# Sheet1.net
KiCad netlist of a schematic drawn in Altium Designer
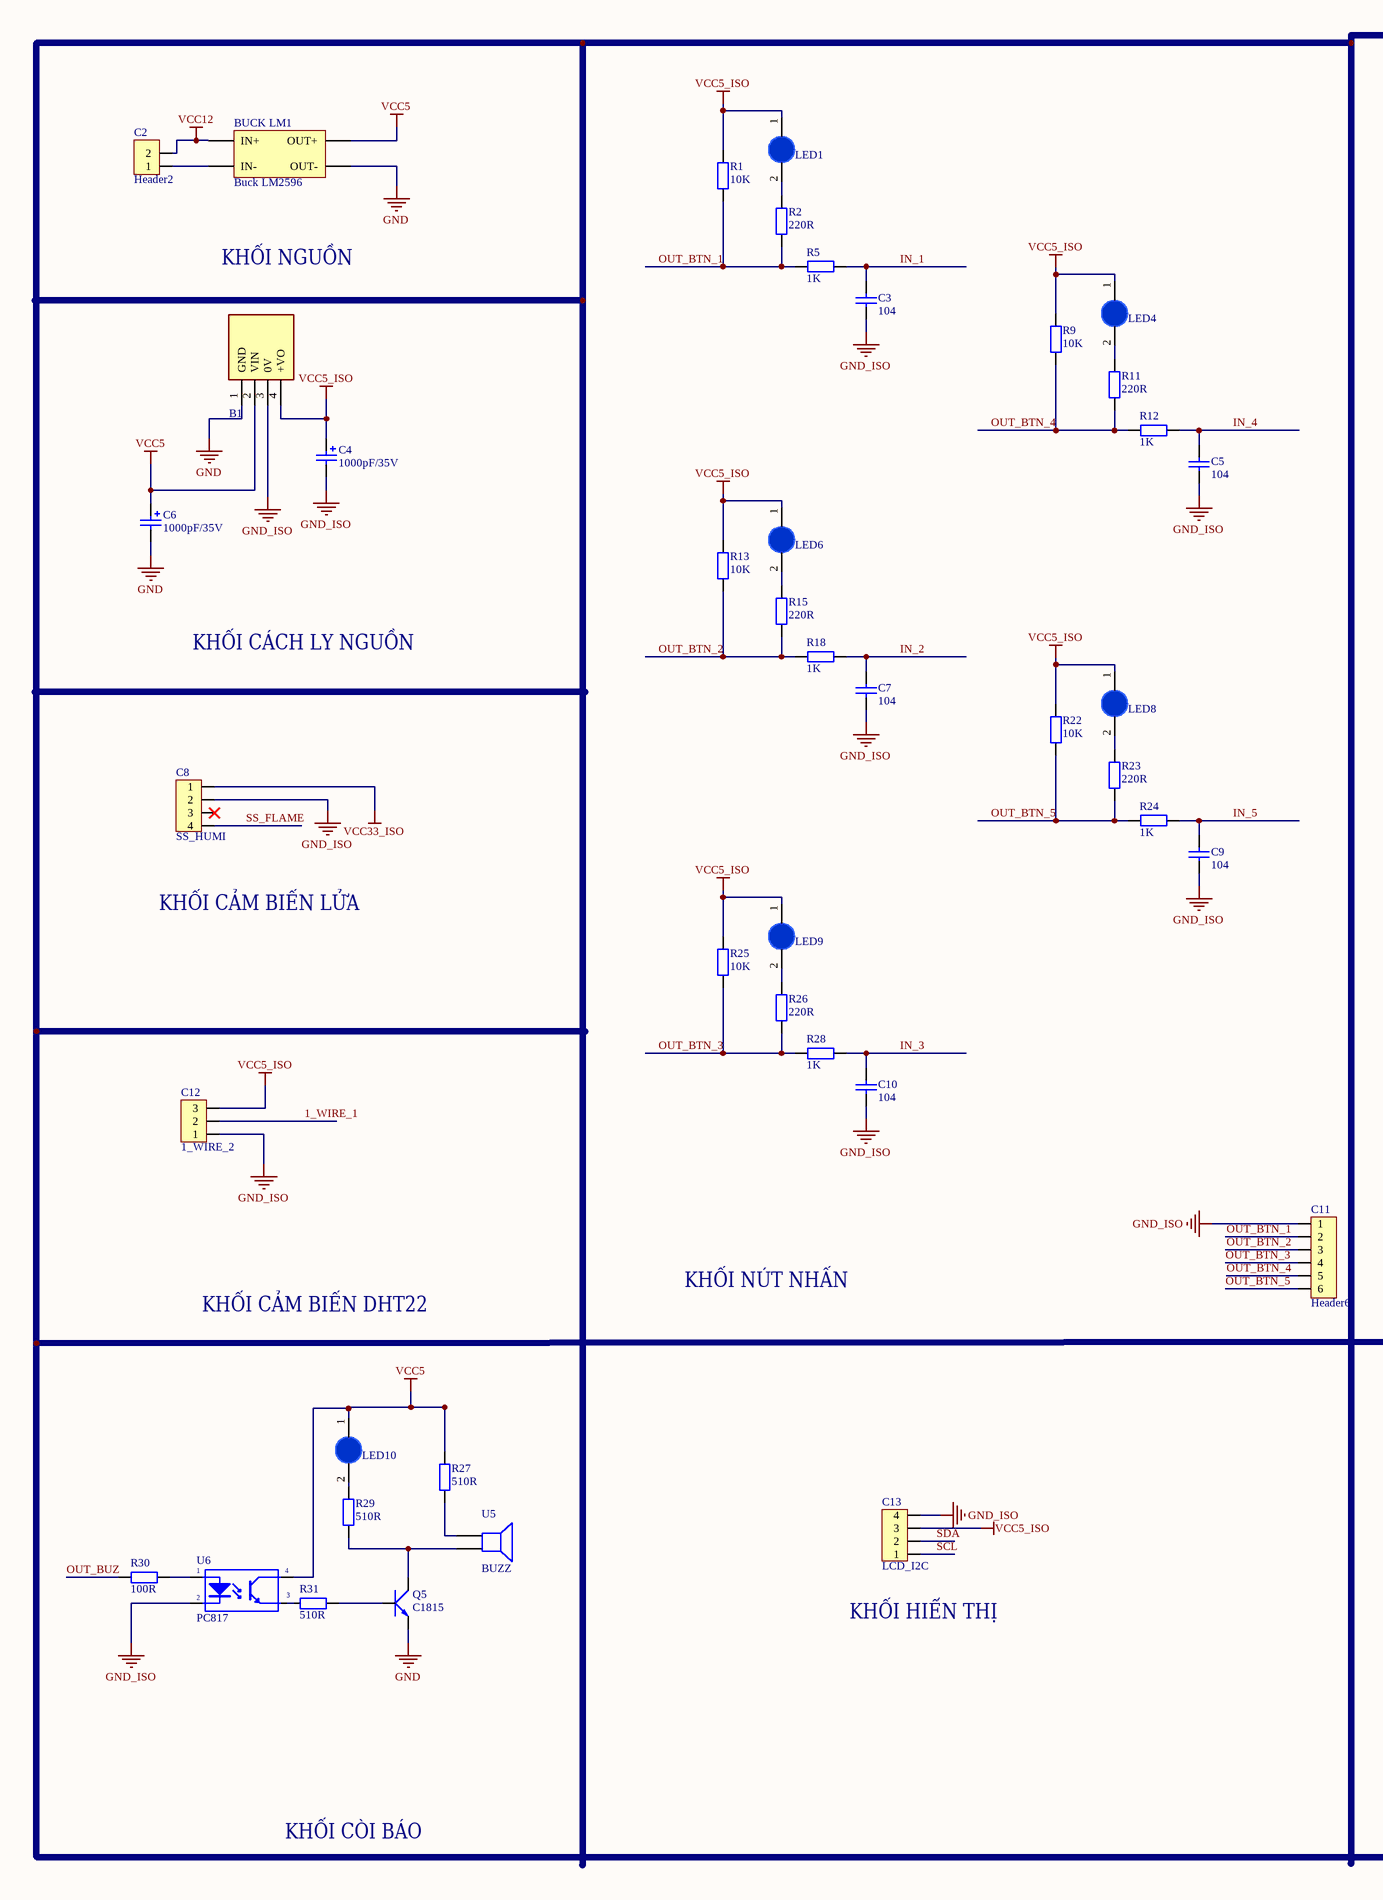
[diagram p0: Sheet1.SchDoc, left]
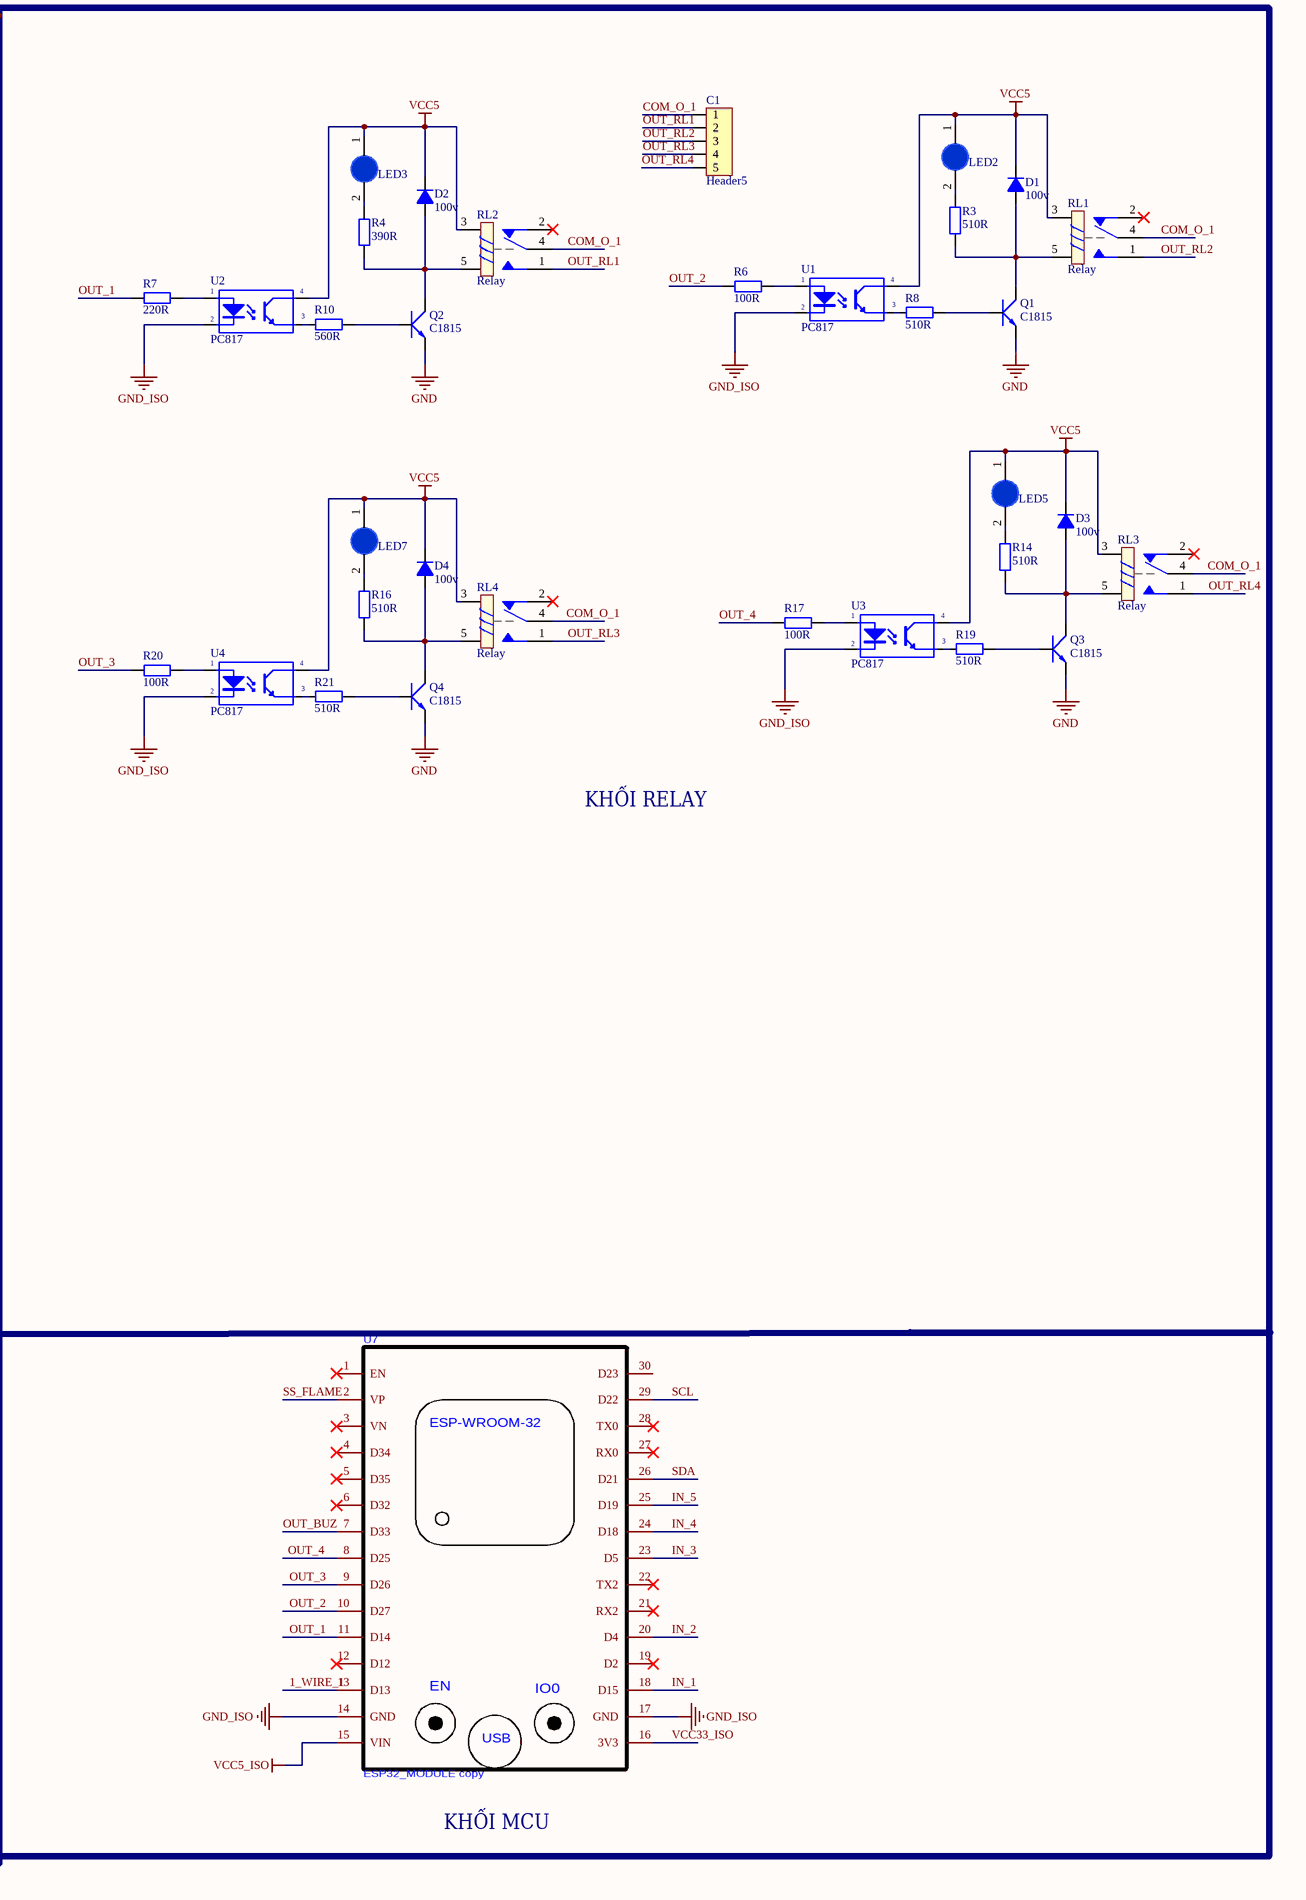
[diagram p1: Sheet1.SchDoc, right]

(export (version "E")
  (design (tool "Eeschema 10.0.6"))
  (components
    (comp (ref "B1")
      (value "B0505S1W")
      (footprint "B0505S1W")
      (description "Power Supply")
      (fields (field (name "MANUFACTURER_PART_NUMBER") "B0505S-1W"))
      (libsource (lib "myLib_v1") (part "B0505S1W"))
    )
    (comp (ref "BUCK LM1")
      (value "Buck LM2596")
      (footprint "BUCK LM2596")
      (libsource (lib "myLib_v1") (part "Buck LM2596"))
    )
    (comp (ref "C1")
      (value "Header5")
      (footprint "Header5")
      (description "Header IDC, 5 x 1 Pin Vertical 2.54mm Pitch (Non-Boxed, Male)")
      (fields
        (field (name "MANUFACTURER") "Würth Elektronik eiSos GmbH")
        (field (name "PARTNO") "613002143121")
        (field (name "CREATED BY") "Karrer Zheng")
      )
      (libsource (lib "myLib_v1") (part "Header5"))
    )
    (comp (ref "C2")
      (value "Header2")
      (footprint "Header2")
      (description "Header IDC, 2 x 1 Pin Vertical 2.54mm Pitch (Non-Boxed, Male)")
      (fields
        (field (name "MANUFACTURER") "Würth Elektronik eiSos GmbH")
        (field (name "PARTNO") "613002143121")
        (field (name "CREATED BY") "Karrer Zheng")
      )
      (libsource (lib "myLib_v1") (part "Header2"))
    )
    (comp (ref "C3")
      (value "104")
      (footprint "tu gom")
      (description "Cắm")
      (libsource (lib "Altium_Lib_by_KhueNguyenCreator") (part "Tu gom 104 50V"))
    )
    (comp (ref "C4")
      (value "1000pF/35V")
      (footprint "CP2/5")
      (description "Polarized Capacitor (Surface Mount)")
      (fields (field (name "Comment") "Cap Pol3") (field (name "PUBLISHER") "Altium Limited"))
      (libsource (lib "myLib_v1") (part "Cap Pol3"))
    )
    (comp (ref "C5")
      (value "104")
      (footprint "tu gom")
      (description "Cắm")
      (libsource (lib "Altium_Lib_by_KhueNguyenCreator") (part "Tu gom 104 50V"))
    )
    (comp (ref "C6")
      (value "1000pF/35V")
      (footprint "CP2/5")
      (description "Polarized Capacitor (Surface Mount)")
      (fields (field (name "Comment") "Cap Pol3") (field (name "PUBLISHER") "Altium Limited"))
      (libsource (lib "myLib_v1") (part "Cap Pol3"))
    )
    (comp (ref "C7")
      (value "104")
      (footprint "tu gom")
      (description "Cắm")
      (libsource (lib "Altium_Lib_by_KhueNguyenCreator") (part "Tu gom 104 50V"))
    )
    (comp (ref "C8")
      (value "SS_HUMI")
      (footprint "Header4")
      (description "Header IDC, 4 x 1 Pin Vertical 2.54mm Pitch (Non-Boxed, Male)")
      (fields
        (field (name "MANUFACTURER") "Würth Elektronik eiSos GmbH")
        (field (name "PARTNO") "613002143121")
        (field (name "CREATED BY") "Karrer Zheng")
      )
      (libsource (lib "myLib_v1") (part "Header4"))
    )
    (comp (ref "C9")
      (value "104")
      (footprint "tu gom")
      (description "Cắm")
      (libsource (lib "Altium_Lib_by_KhueNguyenCreator") (part "Tu gom 104 50V"))
    )
    (comp (ref "C10")
      (value "104")
      (footprint "tu gom")
      (description "Cắm")
      (libsource (lib "Altium_Lib_by_KhueNguyenCreator") (part "Tu gom 104 50V"))
    )
    (comp (ref "C11")
      (value "Header6")
      (footprint "HDR6")
      (description "Header IDC, 6 x 1 Pin Vertical 2.54mm Pitch (Non-Boxed, Male)")
      (fields
        (field (name "MANUFACTURER") "Würth Elektronik eiSos GmbH")
        (field (name "PARTNO") "613002143121")
        (field (name "CREATED BY") "Karrer Zheng")
      )
      (libsource (lib "myLib_v1") (part "Header6"))
    )
    (comp (ref "C12")
      (value "1_WIRE_2")
      (footprint "Header3")
      (description "Header IDC, 3 x 1 Pin Vertical 2.54mm Pitch (Non-Boxed, Male)")
      (fields
        (field (name "MANUFACTURER") "Würth Elektronik eiSos GmbH")
        (field (name "PARTNO") "613002143121")
        (field (name "CREATED BY") "Karrer Zheng")
      )
      (libsource (lib "myLib_v1") (part "Header3"))
    )
    (comp (ref "C13")
      (value "LCD_I2C")
      (footprint "Header4")
      (description "Header IDC, 4 x 1 Pin Vertical 2.54mm Pitch (Non-Boxed, Male)")
      (fields
        (field (name "MANUFACTURER") "Würth Elektronik eiSos GmbH")
        (field (name "PARTNO") "613002143121")
        (field (name "CREATED BY") "Karrer Zheng")
      )
      (libsource (lib "") (part "Header4_1"))
    )
    (comp (ref "D1")
      (value "100v")
      (footprint "DIODE 0.5A")
      (description "Cắm")
      (libsource (lib "Altium_Lib_by_KhueNguyenCreator") (part "Diode 1N4148"))
    )
    (comp (ref "D2")
      (value "100v")
      (footprint "DIODE 0.5A")
      (description "Cắm")
      (libsource (lib "Altium_Lib_by_KhueNguyenCreator") (part "Diode 1N4148"))
    )
    (comp (ref "D3")
      (value "100v")
      (footprint "DIODE 0.5A")
      (description "Cắm")
      (libsource (lib "Altium_Lib_by_KhueNguyenCreator") (part "Diode 1N4148"))
    )
    (comp (ref "D4")
      (value "100v")
      (footprint "DIODE 0.5A")
      (description "Cắm")
      (libsource (lib "Altium_Lib_by_KhueNguyenCreator") (part "Diode 1N4148"))
    )
    (comp (ref "LED1")
      (value "LED 3mm")
      (footprint "LED-3MM-BLUE")
      (description "Cắm")
      (libsource (lib "myLib_v1") (part "LED 3mm Xanh Duong"))
    )
    (comp (ref "LED2")
      (value "LED 3mm")
      (footprint "LED-3MM-BLUE")
      (description "Cắm")
      (libsource (lib "myLib_v1") (part "LED 3mm Xanh Duong"))
    )
    (comp (ref "LED3")
      (value "LED 3mm")
      (footprint "LED-3MM-BLUE")
      (description "Cắm")
      (libsource (lib "myLib_v1") (part "LED 3mm Xanh Duong"))
    )
    (comp (ref "LED4")
      (value "LED 3mm")
      (footprint "LED-3MM-BLUE")
      (description "Cắm")
      (libsource (lib "myLib_v1") (part "LED 3mm Xanh Duong"))
    )
    (comp (ref "LED5")
      (value "LED 3mm")
      (footprint "LED-3MM-BLUE")
      (description "Cắm")
      (libsource (lib "myLib_v1") (part "LED 3mm Xanh Duong"))
    )
    (comp (ref "LED6")
      (value "LED 3mm")
      (footprint "LED-3MM-BLUE")
      (description "Cắm")
      (libsource (lib "myLib_v1") (part "LED 3mm Xanh Duong"))
    )
    (comp (ref "LED7")
      (value "LED 3mm")
      (footprint "LED-3MM-BLUE")
      (description "Cắm")
      (libsource (lib "myLib_v1") (part "LED 3mm Xanh Duong"))
    )
    (comp (ref "LED8")
      (value "LED 3mm")
      (footprint "LED-3MM-BLUE")
      (description "Cắm")
      (libsource (lib "myLib_v1") (part "LED 3mm Xanh Duong"))
    )
    (comp (ref "LED9")
      (value "LED 3mm")
      (footprint "LED-3MM-BLUE")
      (description "Cắm")
      (libsource (lib "myLib_v1") (part "LED 3mm Xanh Duong"))
    )
    (comp (ref "LED10")
      (value "LED 3mm")
      (footprint "LED-3MM-BLUE")
      (description "Cắm")
      (libsource (lib "myLib_v1") (part "LED 3mm Xanh Duong"))
    )
    (comp (ref "Q1")
      (value "C1815")
      (footprint "C1815_cam")
      (description "NPN 600mW, ECB")
      (libsource (lib "myLib_v1") (part "C1815"))
    )
    (comp (ref "Q2")
      (value "C1815")
      (footprint "C1815_cam")
      (description "NPN 600mW, ECB")
      (libsource (lib "myLib_v1") (part "C1815"))
    )
    (comp (ref "Q3")
      (value "C1815")
      (footprint "C1815_cam")
      (description "NPN 600mW, ECB")
      (libsource (lib "myLib_v1") (part "C1815"))
    )
    (comp (ref "Q4")
      (value "C1815")
      (footprint "C1815_cam")
      (description "NPN 600mW, ECB")
      (libsource (lib "myLib_v1") (part "C1815"))
    )
    (comp (ref "Q5")
      (value "C1815")
      (footprint "C1815_cam")
      (description "NPN 600mW, ECB")
      (libsource (lib "myLib_v1") (part "C1815"))
    )
    (comp (ref "R1")
      (value "10K")
      (footprint "R1/4W")
      (description "Resistor 1/4W")
      (libsource (lib "myLib_v1") (part "R1/4W"))
    )
    (comp (ref "R2")
      (value "220R")
      (footprint "R1/4W")
      (description "Resistor 1/4W")
      (libsource (lib "myLib_v1") (part "R1/4W"))
    )
    (comp (ref "R3")
      (value "510R")
      (footprint "R1/4W")
      (description "Resistor 1/4W")
      (libsource (lib "myLib_v1") (part "R1/4W"))
    )
    (comp (ref "R4")
      (value "390R")
      (footprint "R1/4W")
      (description "Resistor 1/4W")
      (libsource (lib "myLib_v1") (part "R1/4W"))
    )
    (comp (ref "R5")
      (value "1K")
      (footprint "R1/4W")
      (description "Resistor 1/4W")
      (libsource (lib "myLib_v1") (part "R1/4W"))
    )
    (comp (ref "R6")
      (value "100R")
      (footprint "R1/4W")
      (description "Resistor 1/4W")
      (libsource (lib "myLib_v1") (part "R1/4W"))
    )
    (comp (ref "R7")
      (value "220R")
      (footprint "R1/4W")
      (description "Resistor 1/4W")
      (libsource (lib "myLib_v1") (part "R1/4W"))
    )
    (comp (ref "R8")
      (value "510R")
      (footprint "R1/4W")
      (description "Resistor 1/4W")
      (libsource (lib "myLib_v1") (part "R1/4W"))
    )
    (comp (ref "R9")
      (value "10K")
      (footprint "R1/4W")
      (description "Resistor 1/4W")
      (libsource (lib "myLib_v1") (part "R1/4W"))
    )
    (comp (ref "R10")
      (value "560R")
      (footprint "R1/4W")
      (description "Resistor 1/4W")
      (libsource (lib "myLib_v1") (part "R1/4W"))
    )
    (comp (ref "R11")
      (value "220R")
      (footprint "R1/4W")
      (description "Resistor 1/4W")
      (libsource (lib "myLib_v1") (part "R1/4W"))
    )
    (comp (ref "R12")
      (value "1K")
      (footprint "R1/4W")
      (description "Resistor 1/4W")
      (libsource (lib "myLib_v1") (part "R1/4W"))
    )
    (comp (ref "R13")
      (value "10K")
      (footprint "R1/4W")
      (description "Resistor 1/4W")
      (libsource (lib "myLib_v1") (part "R1/4W"))
    )
    (comp (ref "R14")
      (value "510R")
      (footprint "R1/4W")
      (description "Resistor 1/4W")
      (libsource (lib "myLib_v1") (part "R1/4W"))
    )
    (comp (ref "R15")
      (value "220R")
      (footprint "R1/4W")
      (description "Resistor 1/4W")
      (libsource (lib "myLib_v1") (part "R1/4W"))
    )
    (comp (ref "R16")
      (value "510R")
      (footprint "R1/4W")
      (description "Resistor 1/4W")
      (libsource (lib "myLib_v1") (part "R1/4W"))
    )
    (comp (ref "R17")
      (value "100R")
      (footprint "R1/4W")
      (description "Resistor 1/4W")
      (libsource (lib "myLib_v1") (part "R1/4W"))
    )
    (comp (ref "R18")
      (value "1K")
      (footprint "R1/4W")
      (description "Resistor 1/4W")
      (libsource (lib "myLib_v1") (part "R1/4W"))
    )
    (comp (ref "R19")
      (value "510R")
      (footprint "R1/4W")
      (description "Resistor 1/4W")
      (libsource (lib "myLib_v1") (part "R1/4W"))
    )
    (comp (ref "R20")
      (value "100R")
      (footprint "R1/4W")
      (description "Resistor 1/4W")
      (libsource (lib "myLib_v1") (part "R1/4W"))
    )
    (comp (ref "R21")
      (value "510R")
      (footprint "R1/4W")
      (description "Resistor 1/4W")
      (libsource (lib "myLib_v1") (part "R1/4W"))
    )
    (comp (ref "R22")
      (value "10K")
      (footprint "R1/4W")
      (description "Resistor 1/4W")
      (libsource (lib "myLib_v1") (part "R1/4W"))
    )
    (comp (ref "R23")
      (value "220R")
      (footprint "R1/4W")
      (description "Resistor 1/4W")
      (libsource (lib "myLib_v1") (part "R1/4W"))
    )
    (comp (ref "R24")
      (value "1K")
      (footprint "R1/4W")
      (description "Resistor 1/4W")
      (libsource (lib "myLib_v1") (part "R1/4W"))
    )
    (comp (ref "R25")
      (value "10K")
      (footprint "R1/4W")
      (description "Resistor 1/4W")
      (libsource (lib "myLib_v1") (part "R1/4W"))
    )
    (comp (ref "R26")
      (value "220R")
      (footprint "R1/4W")
      (description "Resistor 1/4W")
      (libsource (lib "myLib_v1") (part "R1/4W"))
    )
    (comp (ref "R27")
      (value "510R")
      (footprint "R1/4W")
      (description "Resistor 1/4W")
      (libsource (lib "myLib_v1") (part "R1/4W"))
    )
    (comp (ref "R28")
      (value "1K")
      (footprint "R1/4W")
      (description "Resistor 1/4W")
      (libsource (lib "myLib_v1") (part "R1/4W"))
    )
    (comp (ref "R29")
      (value "510R")
      (footprint "R1/4W")
      (description "Resistor 1/4W")
      (libsource (lib "myLib_v1") (part "R1/4W"))
    )
    (comp (ref "R30")
      (value "100R")
      (footprint "R1/4W")
      (description "Resistor 1/4W")
      (libsource (lib "myLib_v1") (part "R1/4W"))
    )
    (comp (ref "R31")
      (value "510R")
      (footprint "R1/4W")
      (description "Resistor 1/4W")
      (libsource (lib "myLib_v1") (part "R1/4W"))
    )
    (comp (ref "RL1")
      (value "Relay")
      (footprint "RELAY_SRA_05VDC_SL_C")
      (description "Relay 5 Chan")
      (libsource (lib "myLib_v1") (part "RL_SRA-05VDC-SL-C"))
    )
    (comp (ref "RL2")
      (value "Relay")
      (footprint "RELAY_SRA_05VDC_SL_C")
      (description "Relay 5 Chan")
      (libsource (lib "myLib_v1") (part "RL_SRA-05VDC-SL-C"))
    )
    (comp (ref "RL3")
      (value "Relay")
      (footprint "RELAY_SRA_05VDC_SL_C")
      (description "Relay 5 Chan")
      (libsource (lib "myLib_v1") (part "RL_SRA-05VDC-SL-C"))
    )
    (comp (ref "RL4")
      (value "Relay")
      (footprint "RELAY_SRA_05VDC_SL_C")
      (description "Relay 5 Chan")
      (libsource (lib "myLib_v1") (part "RL_SRA-05VDC-SL-C"))
    )
    (comp (ref "U1")
      (value "PC817")
      (footprint "DIP4/W0.3")
      (description "Single Opto")
      (libsource (lib "myLib_v1") (part "PC817"))
    )
    (comp (ref "U2")
      (value "PC817")
      (footprint "DIP4/W0.3")
      (description "Single Opto")
      (libsource (lib "myLib_v1") (part "PC817"))
    )
    (comp (ref "U3")
      (value "PC817")
      (footprint "DIP4/W0.3")
      (description "Single Opto")
      (libsource (lib "myLib_v1") (part "PC817"))
    )
    (comp (ref "U4")
      (value "PC817")
      (footprint "DIP4/W0.3")
      (description "Single Opto")
      (libsource (lib "myLib_v1") (part "PC817"))
    )
    (comp (ref "U5")
      (value "BUZZ")
      (footprint "BUZZER_D9_TH")
      (description "Loudspeaker")
      (libsource (lib "BYTECH_HW_LIB_2019 (1)") (part "Speaker"))
    )
    (comp (ref "U6")
      (value "PC817")
      (footprint "DIP4/W0.3")
      (description "Single Opto")
      (libsource (lib "myLib_v1") (part "PC817"))
    )
    (comp (ref "U7")
      (value "ESP32_MODULE copy")
      (footprint "ESP32-WIFIMODULE-FOOTPRINT")
      (libsource (lib "myLib_v1") (part "ESP32_MODULE copy"))
    )
  )
  (nets
    (net (code "1") (name "/1_WIRE_1") (class "Default")
      (node (ref "C12") (pin "2") (pinfunction "2_2") (pintype "passive"))
      (node (ref "U7") (pin "13") (pinfunction "D13_13") (pintype "passive"))
    )
    (net (code "2") (name "/COM_O_1") (class "Default")
      (node (ref "C1") (pin "1") (pinfunction "1_1") (pintype "passive"))
      (node (ref "RL1") (pin "4") (pinfunction "4_4") (pintype "passive"))
      (node (ref "RL2") (pin "4") (pinfunction "4_4") (pintype "passive"))
      (node (ref "RL3") (pin "4") (pinfunction "4_4") (pintype "passive"))
      (node (ref "RL4") (pin "4") (pinfunction "4_4") (pintype "passive"))
    )
    (net (code "3") (name "/IN_1") (class "Default")
      (node (ref "C3") (pin "1") (pinfunction "1_1") (pintype "passive"))
      (node (ref "R5") (pin "1") (pinfunction "1_1") (pintype "passive"))
      (node (ref "U7") (pin "18") (pinfunction "D15_18") (pintype "passive"))
    )
    (net (code "4") (name "/IN_2") (class "Default")
      (node (ref "C7") (pin "1") (pinfunction "1_1") (pintype "passive"))
      (node (ref "R18") (pin "1") (pinfunction "1_1") (pintype "passive"))
      (node (ref "U7") (pin "20") (pinfunction "D4_20") (pintype "passive"))
    )
    (net (code "5") (name "/IN_3") (class "Default")
      (node (ref "C10") (pin "1") (pinfunction "1_1") (pintype "passive"))
      (node (ref "R28") (pin "1") (pinfunction "1_1") (pintype "passive"))
      (node (ref "U7") (pin "23") (pinfunction "D5_23") (pintype "passive"))
    )
    (net (code "6") (name "/IN_4") (class "Default")
      (node (ref "C5") (pin "1") (pinfunction "1_1") (pintype "passive"))
      (node (ref "R12") (pin "1") (pinfunction "1_1") (pintype "passive"))
      (node (ref "U7") (pin "24") (pinfunction "D18_24") (pintype "passive"))
    )
    (net (code "7") (name "/IN_5") (class "Default")
      (node (ref "C9") (pin "1") (pinfunction "1_1") (pintype "passive"))
      (node (ref "R24") (pin "1") (pinfunction "1_1") (pintype "passive"))
      (node (ref "U7") (pin "25") (pinfunction "D19_25") (pintype "passive"))
    )
    (net (code "8") (name "/OUT_1") (class "Default")
      (node (ref "R7") (pin "1") (pinfunction "1_1") (pintype "passive"))
      (node (ref "U7") (pin "11") (pinfunction "D14_11") (pintype "passive"))
    )
    (net (code "9") (name "/OUT_2") (class "Default")
      (node (ref "R6") (pin "1") (pinfunction "1_1") (pintype "passive"))
      (node (ref "U7") (pin "10") (pinfunction "D27_10") (pintype "passive"))
    )
    (net (code "10") (name "/OUT_3") (class "Default")
      (node (ref "R20") (pin "1") (pinfunction "1_1") (pintype "passive"))
      (node (ref "U7") (pin "9") (pinfunction "D26_9") (pintype "passive"))
    )
    (net (code "11") (name "/OUT_4") (class "Default")
      (node (ref "R17") (pin "1") (pinfunction "1_1") (pintype "passive"))
      (node (ref "U7") (pin "8") (pinfunction "D25_8") (pintype "passive"))
    )
    (net (code "12") (name "/OUT_BTN_1") (class "Default")
      (node (ref "C11") (pin "2") (pinfunction "2_2") (pintype "passive"))
      (node (ref "R1") (pin "1") (pinfunction "1_1") (pintype "passive"))
      (node (ref "R2") (pin "1") (pinfunction "1_1") (pintype "passive"))
      (node (ref "R5") (pin "2") (pinfunction "2_2") (pintype "passive"))
    )
    (net (code "13") (name "/OUT_BTN_2") (class "Default")
      (node (ref "C11") (pin "3") (pinfunction "3_3") (pintype "passive"))
      (node (ref "R13") (pin "1") (pinfunction "1_1") (pintype "passive"))
      (node (ref "R15") (pin "1") (pinfunction "1_1") (pintype "passive"))
      (node (ref "R18") (pin "2") (pinfunction "2_2") (pintype "passive"))
    )
    (net (code "14") (name "/OUT_BTN_3") (class "Default")
      (node (ref "C11") (pin "4") (pinfunction "4_4") (pintype "passive"))
      (node (ref "R25") (pin "1") (pinfunction "1_1") (pintype "passive"))
      (node (ref "R26") (pin "1") (pinfunction "1_1") (pintype "passive"))
      (node (ref "R28") (pin "2") (pinfunction "2_2") (pintype "passive"))
    )
    (net (code "15") (name "/OUT_BTN_4") (class "Default")
      (node (ref "C11") (pin "5") (pinfunction "5_5") (pintype "passive"))
      (node (ref "R11") (pin "1") (pinfunction "1_1") (pintype "passive"))
      (node (ref "R12") (pin "2") (pinfunction "2_2") (pintype "passive"))
      (node (ref "R9") (pin "1") (pinfunction "1_1") (pintype "passive"))
    )
    (net (code "16") (name "/OUT_BTN_5") (class "Default")
      (node (ref "C11") (pin "6") (pinfunction "6_6") (pintype "passive"))
      (node (ref "R22") (pin "1") (pinfunction "1_1") (pintype "passive"))
      (node (ref "R23") (pin "1") (pinfunction "1_1") (pintype "passive"))
      (node (ref "R24") (pin "2") (pinfunction "2_2") (pintype "passive"))
    )
    (net (code "17") (name "/OUT_BUZ") (class "Default")
      (node (ref "R30") (pin "1") (pinfunction "1_1") (pintype "passive"))
      (node (ref "U7") (pin "7") (pinfunction "D33_7") (pintype "passive"))
    )
    (net (code "18") (name "/OUT_RL1") (class "Default")
      (node (ref "C1") (pin "2") (pinfunction "2_2") (pintype "passive"))
      (node (ref "RL2") (pin "1") (pinfunction "1_1") (pintype "passive"))
    )
    (net (code "19") (name "/OUT_RL2") (class "Default")
      (node (ref "C1") (pin "3") (pinfunction "3_3") (pintype "passive"))
      (node (ref "RL1") (pin "1") (pinfunction "1_1") (pintype "passive"))
    )
    (net (code "20") (name "/OUT_RL3") (class "Default")
      (node (ref "C1") (pin "4") (pinfunction "4_4") (pintype "passive"))
      (node (ref "RL4") (pin "1") (pinfunction "1_1") (pintype "passive"))
    )
    (net (code "21") (name "/OUT_RL4") (class "Default")
      (node (ref "C1") (pin "5") (pinfunction "5_5") (pintype "passive"))
      (node (ref "RL3") (pin "1") (pinfunction "1_1") (pintype "passive"))
    )
    (net (code "22") (name "/SCL") (class "Default")
      (node (ref "C13") (pin "1") (pinfunction "1_1") (pintype "passive"))
      (node (ref "U7") (pin "29") (pinfunction "D22_29") (pintype "passive"))
    )
    (net (code "23") (name "/SDA") (class "Default")
      (node (ref "C13") (pin "2") (pinfunction "2_2") (pintype "passive"))
      (node (ref "U7") (pin "26") (pinfunction "D21_26") (pintype "passive"))
    )
    (net (code "24") (name "/SS_FLAME") (class "Default")
      (node (ref "C8") (pin "4") (pinfunction "4_4") (pintype "passive"))
      (node (ref "U7") (pin "2") (pinfunction "VP_2") (pintype "passive"))
    )
    (net (code "25") (name "GND") (class "Default")
      (node (ref "B1") (pin "1") (pinfunction "GND_1") (pintype "passive"))
      (node (ref "BUCK LM1") (pin "3") (pinfunction "OUT-_3") (pintype "passive"))
      (node (ref "C6") (pin "2") (pinfunction "2_2") (pintype "passive"))
      (node (ref "Q1") (pin "1") (pinfunction "E_1") (pintype "passive"))
      (node (ref "Q2") (pin "1") (pinfunction "E_1") (pintype "passive"))
      (node (ref "Q3") (pin "1") (pinfunction "E_1") (pintype "passive"))
      (node (ref "Q4") (pin "1") (pinfunction "E_1") (pintype "passive"))
      (node (ref "Q5") (pin "1") (pinfunction "E_1") (pintype "passive"))
    )
    (net (code "26") (name "GND_ISO") (class "Default")
      (node (ref "B1") (pin "3") (pinfunction "0V_3") (pintype "passive"))
      (node (ref "C10") (pin "2") (pinfunction "2_2") (pintype "passive"))
      (node (ref "C11") (pin "1") (pinfunction "1_1") (pintype "passive"))
      (node (ref "C12") (pin "1") (pinfunction "1_1") (pintype "passive"))
      (node (ref "C13") (pin "4") (pinfunction "4_4") (pintype "passive"))
      (node (ref "C3") (pin "2") (pinfunction "2_2") (pintype "passive"))
      (node (ref "C4") (pin "2") (pinfunction "2_2") (pintype "passive"))
      (node (ref "C5") (pin "2") (pinfunction "2_2") (pintype "passive"))
      (node (ref "C7") (pin "2") (pinfunction "2_2") (pintype "passive"))
      (node (ref "C8") (pin "2") (pinfunction "2_2") (pintype "passive"))
      (node (ref "C9") (pin "2") (pinfunction "2_2") (pintype "passive"))
      (node (ref "U1") (pin "2") (pinfunction "K_2") (pintype "passive"))
      (node (ref "U2") (pin "2") (pinfunction "K_2") (pintype "passive"))
      (node (ref "U3") (pin "2") (pinfunction "K_2") (pintype "passive"))
      (node (ref "U4") (pin "2") (pinfunction "K_2") (pintype "passive"))
      (node (ref "U6") (pin "2") (pinfunction "K_2") (pintype "passive"))
      (node (ref "U7") (pin "14") (pinfunction "GND_14") (pintype "passive"))
      (node (ref "U7") (pin "17") (pinfunction "GND_17") (pintype "passive"))
    )
    (net (code "27") (name "Net-(BUCK LM1-IN-)") (class "Default")
      (node (ref "BUCK LM1") (pin "2") (pinfunction "IN-_2") (pintype "passive"))
      (node (ref "C2") (pin "1") (pinfunction "1_1") (pintype "passive"))
    )
    (net (code "28") (name "Net-(D1-A)") (class "Default")
      (node (ref "D1") (pin "1") (pinfunction "A_1") (pintype "passive"))
      (node (ref "Q1") (pin "2") (pinfunction "C_2") (pintype "passive"))
      (node (ref "R3") (pin "2") (pinfunction "2_2") (pintype "passive"))
      (node (ref "RL1") (pin "5") (pinfunction "5_5") (pintype "passive"))
    )
    (net (code "29") (name "Net-(D2-A)") (class "Default")
      (node (ref "D2") (pin "1") (pinfunction "A_1") (pintype "passive"))
      (node (ref "Q2") (pin "2") (pinfunction "C_2") (pintype "passive"))
      (node (ref "R4") (pin "2") (pinfunction "2_2") (pintype "passive"))
      (node (ref "RL2") (pin "5") (pinfunction "5_5") (pintype "passive"))
    )
    (net (code "30") (name "Net-(D3-A)") (class "Default")
      (node (ref "D3") (pin "1") (pinfunction "A_1") (pintype "passive"))
      (node (ref "Q3") (pin "2") (pinfunction "C_2") (pintype "passive"))
      (node (ref "R14") (pin "2") (pinfunction "2_2") (pintype "passive"))
      (node (ref "RL3") (pin "5") (pinfunction "5_5") (pintype "passive"))
    )
    (net (code "31") (name "Net-(D4-A)") (class "Default")
      (node (ref "D4") (pin "1") (pinfunction "A_1") (pintype "passive"))
      (node (ref "Q4") (pin "2") (pinfunction "C_2") (pintype "passive"))
      (node (ref "R16") (pin "2") (pinfunction "2_2") (pintype "passive"))
      (node (ref "RL4") (pin "5") (pinfunction "5_5") (pintype "passive"))
    )
    (net (code "32") (name "Net-(LED1-K)") (class "Default")
      (node (ref "LED1") (pin "2") (pinfunction "K_2") (pintype "passive"))
      (node (ref "R2") (pin "2") (pinfunction "2_2") (pintype "passive"))
    )
    (net (code "33") (name "Net-(LED2-K)") (class "Default")
      (node (ref "LED2") (pin "2") (pinfunction "K_2") (pintype "passive"))
      (node (ref "R3") (pin "1") (pinfunction "1_1") (pintype "passive"))
    )
    (net (code "34") (name "Net-(LED3-K)") (class "Default")
      (node (ref "LED3") (pin "2") (pinfunction "K_2") (pintype "passive"))
      (node (ref "R4") (pin "1") (pinfunction "1_1") (pintype "passive"))
    )
    (net (code "35") (name "Net-(LED4-K)") (class "Default")
      (node (ref "LED4") (pin "2") (pinfunction "K_2") (pintype "passive"))
      (node (ref "R11") (pin "2") (pinfunction "2_2") (pintype "passive"))
    )
    (net (code "36") (name "Net-(LED5-K)") (class "Default")
      (node (ref "LED5") (pin "2") (pinfunction "K_2") (pintype "passive"))
      (node (ref "R14") (pin "1") (pinfunction "1_1") (pintype "passive"))
    )
    (net (code "37") (name "Net-(LED6-K)") (class "Default")
      (node (ref "LED6") (pin "2") (pinfunction "K_2") (pintype "passive"))
      (node (ref "R15") (pin "2") (pinfunction "2_2") (pintype "passive"))
    )
    (net (code "38") (name "Net-(LED7-K)") (class "Default")
      (node (ref "LED7") (pin "2") (pinfunction "K_2") (pintype "passive"))
      (node (ref "R16") (pin "1") (pinfunction "1_1") (pintype "passive"))
    )
    (net (code "39") (name "Net-(LED8-K)") (class "Default")
      (node (ref "LED8") (pin "2") (pinfunction "K_2") (pintype "passive"))
      (node (ref "R23") (pin "2") (pinfunction "2_2") (pintype "passive"))
    )
    (net (code "40") (name "Net-(LED9-K)") (class "Default")
      (node (ref "LED9") (pin "2") (pinfunction "K_2") (pintype "passive"))
      (node (ref "R26") (pin "2") (pinfunction "2_2") (pintype "passive"))
    )
    (net (code "41") (name "Net-(LED10-K)") (class "Default")
      (node (ref "LED10") (pin "2") (pinfunction "K_2") (pintype "passive"))
      (node (ref "R29") (pin "1") (pinfunction "1_1") (pintype "passive"))
    )
    (net (code "42") (name "Net-(Q1-B)") (class "Default")
      (node (ref "Q1") (pin "3") (pinfunction "B_3") (pintype "passive"))
      (node (ref "R8") (pin "2") (pinfunction "2_2") (pintype "passive"))
    )
    (net (code "43") (name "Net-(Q2-B)") (class "Default")
      (node (ref "Q2") (pin "3") (pinfunction "B_3") (pintype "passive"))
      (node (ref "R10") (pin "2") (pinfunction "2_2") (pintype "passive"))
    )
    (net (code "44") (name "Net-(Q3-B)") (class "Default")
      (node (ref "Q3") (pin "3") (pinfunction "B_3") (pintype "passive"))
      (node (ref "R19") (pin "2") (pinfunction "2_2") (pintype "passive"))
    )
    (net (code "45") (name "Net-(Q4-B)") (class "Default")
      (node (ref "Q4") (pin "3") (pinfunction "B_3") (pintype "passive"))
      (node (ref "R21") (pin "2") (pinfunction "2_2") (pintype "passive"))
    )
    (net (code "46") (name "Net-(Q5-B)") (class "Default")
      (node (ref "Q5") (pin "3") (pinfunction "B_3") (pintype "passive"))
      (node (ref "R31") (pin "2") (pinfunction "2_2") (pintype "passive"))
    )
    (net (code "47") (name "Net-(Q5-C)") (class "Default")
      (node (ref "Q5") (pin "2") (pinfunction "C_2") (pintype "passive"))
      (node (ref "R29") (pin "2") (pinfunction "2_2") (pintype "passive"))
      (node (ref "U5") (pin "2") (pinfunction "2_2") (pintype "passive"))
    )
    (net (code "48") (name "Net-(R27-Pad2)") (class "Default")
      (node (ref "R27") (pin "2") (pinfunction "2_2") (pintype "passive"))
      (node (ref "U5") (pin "1") (pinfunction "1_1") (pintype "passive"))
    )
    (net (code "49") (name "Net-(U1-A)") (class "Default")
      (node (ref "R6") (pin "2") (pinfunction "2_2") (pintype "passive"))
      (node (ref "U1") (pin "1") (pinfunction "A_1") (pintype "passive"))
    )
    (net (code "50") (name "Net-(U1-E)") (class "Default")
      (node (ref "R8") (pin "1") (pinfunction "1_1") (pintype "passive"))
      (node (ref "U1") (pin "3") (pinfunction "E_3") (pintype "passive"))
    )
    (net (code "51") (name "Net-(U2-A)") (class "Default")
      (node (ref "R7") (pin "2") (pinfunction "2_2") (pintype "passive"))
      (node (ref "U2") (pin "1") (pinfunction "A_1") (pintype "passive"))
    )
    (net (code "52") (name "Net-(U2-E)") (class "Default")
      (node (ref "R10") (pin "1") (pinfunction "1_1") (pintype "passive"))
      (node (ref "U2") (pin "3") (pinfunction "E_3") (pintype "passive"))
    )
    (net (code "53") (name "Net-(U3-A)") (class "Default")
      (node (ref "R17") (pin "2") (pinfunction "2_2") (pintype "passive"))
      (node (ref "U3") (pin "1") (pinfunction "A_1") (pintype "passive"))
    )
    (net (code "54") (name "Net-(U3-E)") (class "Default")
      (node (ref "R19") (pin "1") (pinfunction "1_1") (pintype "passive"))
      (node (ref "U3") (pin "3") (pinfunction "E_3") (pintype "passive"))
    )
    (net (code "55") (name "Net-(U4-A)") (class "Default")
      (node (ref "R20") (pin "2") (pinfunction "2_2") (pintype "passive"))
      (node (ref "U4") (pin "1") (pinfunction "A_1") (pintype "passive"))
    )
    (net (code "56") (name "Net-(U4-E)") (class "Default")
      (node (ref "R21") (pin "1") (pinfunction "1_1") (pintype "passive"))
      (node (ref "U4") (pin "3") (pinfunction "E_3") (pintype "passive"))
    )
    (net (code "57") (name "Net-(U6-A)") (class "Default")
      (node (ref "R30") (pin "2") (pinfunction "2_2") (pintype "passive"))
      (node (ref "U6") (pin "1") (pinfunction "A_1") (pintype "passive"))
    )
    (net (code "58") (name "Net-(U6-E)") (class "Default")
      (node (ref "R31") (pin "1") (pinfunction "1_1") (pintype "passive"))
      (node (ref "U6") (pin "3") (pinfunction "E_3") (pintype "passive"))
    )
    (net (code "59") (name "VCC5") (class "Default")
      (node (ref "B1") (pin "2") (pinfunction "VIN_2") (pintype "passive"))
      (node (ref "BUCK LM1") (pin "4") (pinfunction "OUT+_4") (pintype "passive"))
      (node (ref "C6") (pin "1") (pinfunction "1_1") (pintype "passive"))
      (node (ref "D1") (pin "2") (pinfunction "K_2") (pintype "passive"))
      (node (ref "D2") (pin "2") (pinfunction "K_2") (pintype "passive"))
      (node (ref "D3") (pin "2") (pinfunction "K_2") (pintype "passive"))
      (node (ref "D4") (pin "2") (pinfunction "K_2") (pintype "passive"))
      (node (ref "LED10") (pin "1") (pinfunction "A_1") (pintype "passive"))
      (node (ref "LED2") (pin "1") (pinfunction "A_1") (pintype "passive"))
      (node (ref "LED3") (pin "1") (pinfunction "A_1") (pintype "passive"))
      (node (ref "LED5") (pin "1") (pinfunction "A_1") (pintype "passive"))
      (node (ref "LED7") (pin "1") (pinfunction "A_1") (pintype "passive"))
      (node (ref "R27") (pin "1") (pinfunction "1_1") (pintype "passive"))
      (node (ref "RL1") (pin "3") (pinfunction "3_3") (pintype "passive"))
      (node (ref "RL2") (pin "3") (pinfunction "3_3") (pintype "passive"))
      (node (ref "RL3") (pin "3") (pinfunction "3_3") (pintype "passive"))
      (node (ref "RL4") (pin "3") (pinfunction "3_3") (pintype "passive"))
      (node (ref "U1") (pin "4") (pinfunction "C_4") (pintype "passive"))
      (node (ref "U2") (pin "4") (pinfunction "C_4") (pintype "passive"))
      (node (ref "U3") (pin "4") (pinfunction "C_4") (pintype "passive"))
      (node (ref "U4") (pin "4") (pinfunction "C_4") (pintype "passive"))
      (node (ref "U6") (pin "4") (pinfunction "C_4") (pintype "passive"))
    )
    (net (code "60") (name "VCC5_ISO") (class "Default")
      (node (ref "B1") (pin "4") (pinfunction "+VO_4") (pintype "passive"))
      (node (ref "C12") (pin "3") (pinfunction "3_3") (pintype "passive"))
      (node (ref "C13") (pin "3") (pinfunction "3_3") (pintype "passive"))
      (node (ref "C4") (pin "1") (pinfunction "1_1") (pintype "passive"))
      (node (ref "LED1") (pin "1") (pinfunction "A_1") (pintype "passive"))
      (node (ref "LED4") (pin "1") (pinfunction "A_1") (pintype "passive"))
      (node (ref "LED6") (pin "1") (pinfunction "A_1") (pintype "passive"))
      (node (ref "LED8") (pin "1") (pinfunction "A_1") (pintype "passive"))
      (node (ref "LED9") (pin "1") (pinfunction "A_1") (pintype "passive"))
      (node (ref "R1") (pin "2") (pinfunction "2_2") (pintype "passive"))
      (node (ref "R13") (pin "2") (pinfunction "2_2") (pintype "passive"))
      (node (ref "R22") (pin "2") (pinfunction "2_2") (pintype "passive"))
      (node (ref "R25") (pin "2") (pinfunction "2_2") (pintype "passive"))
      (node (ref "R9") (pin "2") (pinfunction "2_2") (pintype "passive"))
      (node (ref "U7") (pin "15") (pinfunction "VIN_15") (pintype "passive"))
    )
    (net (code "61") (name "VCC12") (class "Default")
      (node (ref "BUCK LM1") (pin "1") (pinfunction "IN+_1") (pintype "passive"))
      (node (ref "C2") (pin "2") (pinfunction "2_2") (pintype "passive"))
    )
    (net (code "62") (name "VCC33_ISO") (class "Default")
      (node (ref "C8") (pin "1") (pinfunction "1_1") (pintype "passive"))
      (node (ref "U7") (pin "16") (pinfunction "3V3_16") (pintype "passive"))
    )
    (net (code "63") (name "unconnected-(C8-Pad3)") (class "Default")
      (node (ref "C8") (pin "3") (pinfunction "3_3") (pintype "passive+no_connect"))
    )
    (net (code "64") (name "unconnected-(RL1-Pad2)") (class "Default")
      (node (ref "RL1") (pin "2") (pinfunction "2_2") (pintype "passive+no_connect"))
    )
    (net (code "65") (name "unconnected-(RL2-Pad2)") (class "Default")
      (node (ref "RL2") (pin "2") (pinfunction "2_2") (pintype "passive+no_connect"))
    )
    (net (code "66") (name "unconnected-(RL3-Pad2)") (class "Default")
      (node (ref "RL3") (pin "2") (pinfunction "2_2") (pintype "passive+no_connect"))
    )
    (net (code "67") (name "unconnected-(RL4-Pad2)") (class "Default")
      (node (ref "RL4") (pin "2") (pinfunction "2_2") (pintype "passive+no_connect"))
    )
    (net (code "68") (name "unconnected-(U7-D2-Pad19)") (class "Default")
      (node (ref "U7") (pin "19") (pinfunction "D2_19") (pintype "passive+no_connect"))
    )
    (net (code "69") (name "unconnected-(U7-D12-Pad12)") (class "Default")
      (node (ref "U7") (pin "12") (pinfunction "D12_12") (pintype "passive+no_connect"))
    )
    (net (code "70") (name "unconnected-(U7-D23-Pad30)") (class "Default")
      (node (ref "U7") (pin "30") (pinfunction "D23_30") (pintype "passive"))
    )
    (net (code "71") (name "unconnected-(U7-D32-Pad6)") (class "Default")
      (node (ref "U7") (pin "6") (pinfunction "D32_6") (pintype "passive+no_connect"))
    )
    (net (code "72") (name "unconnected-(U7-D34-Pad4)") (class "Default")
      (node (ref "U7") (pin "4") (pinfunction "D34_4") (pintype "passive+no_connect"))
    )
    (net (code "73") (name "unconnected-(U7-D35-Pad5)") (class "Default")
      (node (ref "U7") (pin "5") (pinfunction "D35_5") (pintype "passive+no_connect"))
    )
    (net (code "74") (name "unconnected-(U7-EN-Pad1)") (class "Default")
      (node (ref "U7") (pin "1") (pinfunction "EN_1") (pintype "passive+no_connect"))
    )
    (net (code "75") (name "unconnected-(U7-RX0-Pad27)") (class "Default")
      (node (ref "U7") (pin "27") (pinfunction "RX0_27") (pintype "passive+no_connect"))
    )
    (net (code "76") (name "unconnected-(U7-RX2-Pad21)") (class "Default")
      (node (ref "U7") (pin "21") (pinfunction "RX2_21") (pintype "passive+no_connect"))
    )
    (net (code "77") (name "unconnected-(U7-TX0-Pad28)") (class "Default")
      (node (ref "U7") (pin "28") (pinfunction "TX0_28") (pintype "passive+no_connect"))
    )
    (net (code "78") (name "unconnected-(U7-TX2-Pad22)") (class "Default")
      (node (ref "U7") (pin "22") (pinfunction "TX2_22") (pintype "passive+no_connect"))
    )
    (net (code "79") (name "unconnected-(U7-VN-Pad3)") (class "Default")
      (node (ref "U7") (pin "3") (pinfunction "VN_3") (pintype "passive+no_connect"))
    )
  )
)
